# 411618_029_3_5.net
KiCad netlist of a schematic drawn in Altium Designer
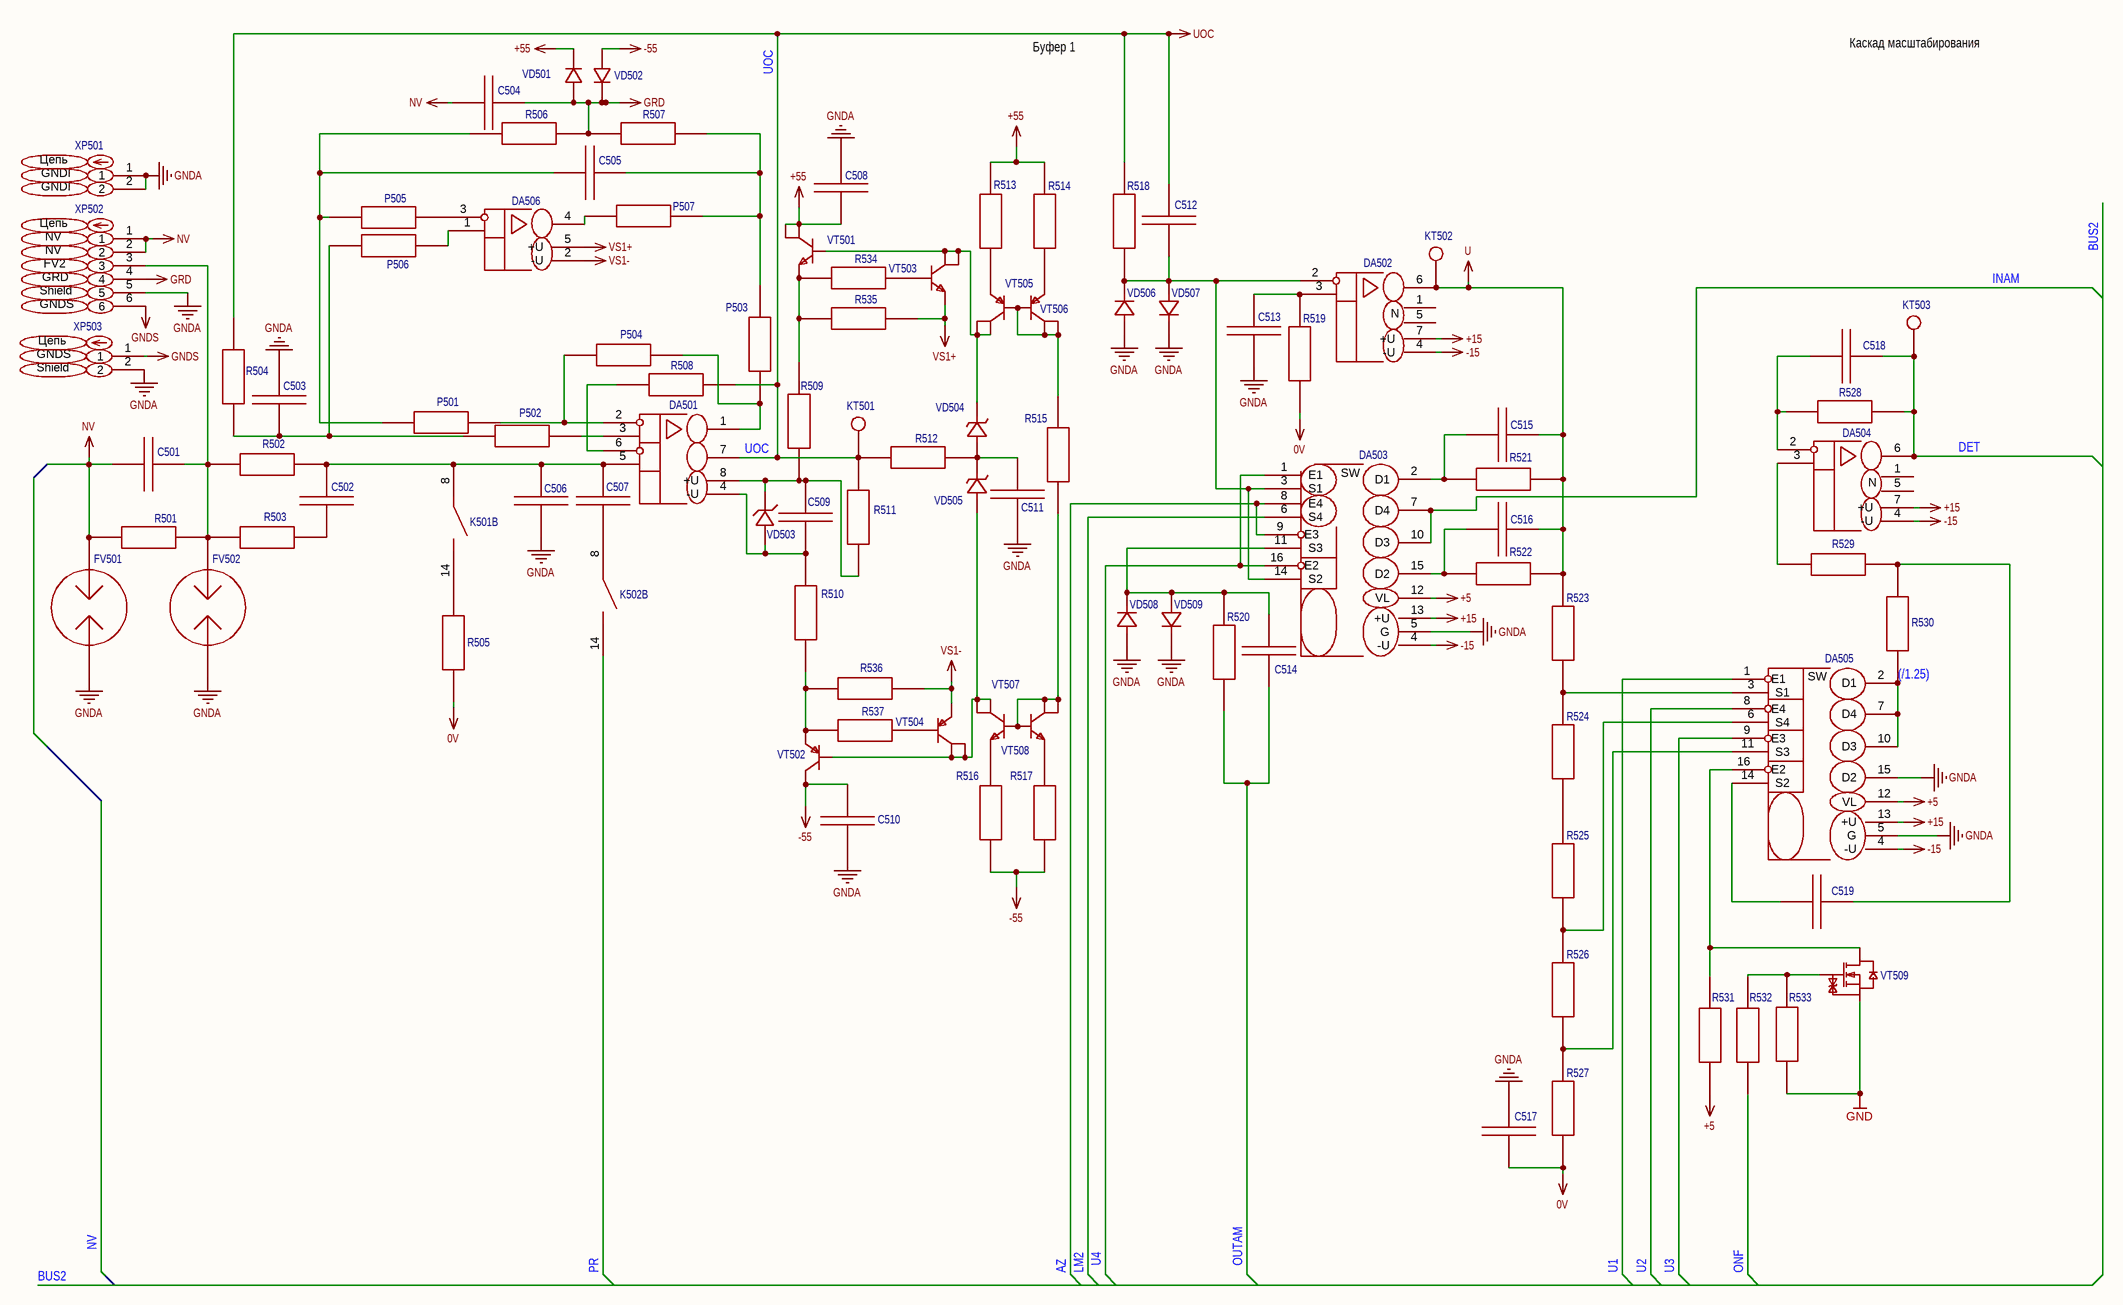
[diagram p0: УШЯИ.411618.029Э Э3 Лист 5.schdoc]

(export (version "E")
  (design (tool "Eeschema 10.0.6"))
  (components
    (comp (ref "C501")
      (value "Конденсатор К10-17Б М47 47пФ  NP0 5% [DIP]")
      (footprint "Конденсатор К10-17Б М47 X.X.xФ  NP0 5% [DIP 8мм]")
      (fields (field (name "MANUFACTURER PART") "К10-17Б М47") (field (name "CONTRIBUTOR") "jordanjin"))
      (libsource (lib "altium-import") (part "root_2_Конденсатор К10-17Б М47 47пФ  NP0 5% [DIP]_"))
    )
    (comp (ref "C502")
      (value "Конденсатор К10-17Б М47 47пФ  NP0 5% [DIP]")
      (footprint "Конденсатор К10-17Б М47 X.X.xФ  NP0 5% [DIP 8мм]")
      (fields (field (name "MANUFACTURER PART") "К10-17Б М47") (field (name "CONTRIBUTOR") "jordanjin"))
      (libsource (lib "altium-import") (part "root_3_Конденсатор К10-17Б М47 47пФ  NP0 5% [DIP]_"))
    )
    (comp (ref "C503")
      (value "Конденсатор SMD 10пФ 100В X7R 10% [0805]")
      (footprint "C0805")
      (fields (field (name "MANUFACTURER PART") "C0805") (field (name "CONTRIBUTOR") "jordanjin"))
      (libsource (lib "altium-import") (part "root_1_Конденсатор SMD 10пФ 100В X7R 10% [0805]_"))
    )
    (comp (ref "C504")
      (value "Конденсатор К10-17Б М47 0,022мкФ  NP0 5% [DIP]")
      (footprint "Конденсатор К10-17Б М47 X.X.xФ  NP0 5% [DIP 5мм]")
      (fields (field (name "MANUFACTURER PART") "К10-17Б М47") (field (name "CONTRIBUTOR") "jordanjin"))
      (libsource (lib "altium-import") (part "root_0_Конденсатор К10-17Б М47 0,022мкФ  NP0 5% [DIP]_"))
    )
    (comp (ref "C505")
      (value "Конденсатор SMD 10пФ 100В X7R 10% [0805]")
      (footprint "C0805")
      (fields (field (name "MANUFACTURER PART") "К10-17Б М47") (field (name "CONTRIBUTOR") "jordanjin"))
      (libsource (lib "altium-import") (part "root_0_Конденсатор К10-17Б М47 10пФ  NP0 5% [DIP]_"))
    )
    (comp (ref "C506")
      (value "Конденсатор К10-17Б М47 33пФ  NP0 5% [DIP]")
      (footprint "Конденсатор К10-17Б М47 X.X.xФ  NP0 5% [DIP 5мм]")
      (fields (field (name "MANUFACTURER PART") "К10-17Б М47") (field (name "CONTRIBUTOR") "jordanjin"))
      (libsource (lib "altium-import") (part "root_3_Конденсатор К10-17Б М47 33пФ  NP0 5% [DIP]_"))
    )
    (comp (ref "C507")
      (value "Конденсатор К10-17Б М47 47пФ  NP0 5% [DIP]")
      (footprint "Конденсатор К10-17Б М47 X.X.xФ  NP0 5% [DIP 5мм]")
      (fields (field (name "MANUFACTURER PART") "К10-17Б М47") (field (name "CONTRIBUTOR") "jordanjin"))
      (libsource (lib "altium-import") (part "root_1_Конденсатор К10-17Б М47 47пФ  NP0 5% [DIP]_"))
    )
    (comp (ref "C508")
      (value "Конденсатор SMD 0,068мкФ 100В X7R 10% [0805]")
      (footprint "C0805")
      (fields (field (name "MANUFACTURER PART") "C0805") (field (name "CONTRIBUTOR") "jordanjin"))
      (libsource (lib "altium-import") (part "root_1_Конденсатор SMD 0,068мкФ 100В X7R 10% [0805]_"))
    )
    (comp (ref "C509")
      (value "Конденсатор SMD 5600пФ 100В X7R 10% [0805]")
      (footprint "C0805")
      (fields (field (name "MANUFACTURER PART") "C0805") (field (name "CONTRIBUTOR") "jordanjin"))
      (libsource (lib "altium-import") (part "root_1_Конденсатор SMD 5600пФ 100В X7R 10% [0805]_"))
    )
    (comp (ref "C510")
      (value "Конденсатор SMD 0,068мкФ 100В X7R 10% [0805]")
      (footprint "C0805")
      (fields (field (name "MANUFACTURER PART") "C0805") (field (name "CONTRIBUTOR") "jordanjin"))
      (libsource (lib "altium-import") (part "root_3_Конденсатор SMD 0,068мкФ 100В X7R 10% [0805]_"))
    )
    (comp (ref "C511")
      (value "Конденсатор SMD 100пФ 100В X7R 10% [0805]")
      (footprint "C0805")
      (fields (field (name "MANUFACTURER PART") "C0805") (field (name "CONTRIBUTOR") "jordanjin"))
      (libsource (lib "altium-import") (part "root_1_Конденсатор SMD 100пФ 100В X7R 10% [0805]_"))
    )
    (comp (ref "C512")
      (value "Конденсатор SMD 10пФ 100В X7R 10% [0805]")
      (footprint "C0805")
      (fields (field (name "MANUFACTURER PART") "C0805") (field (name "CONTRIBUTOR") "jordanjin"))
      (libsource (lib "altium-import") (part "root_1_Конденсатор SMD 10пФ 100В X7R 10% [0805]_"))
    )
    (comp (ref "C513")
      (value "Конденсатор SMD 51пФ 100В X7R 10% [0805]")
      (footprint "C0805")
      (fields (field (name "MANUFACTURER PART") "C0805") (field (name "CONTRIBUTOR") "jordanjin"))
      (libsource (lib "altium-import") (part "root_3_Конденсатор SMD 51пФ 100В X7R 10% [0805]_"))
    )
    (comp (ref "C514")
      (value "Конденсатор SMD 1500пФ 100В X7R 10% [0805]")
      (footprint "C0805")
      (fields (field (name "MANUFACTURER PART") "C0805") (field (name "CONTRIBUTOR") "jordanjin"))
      (libsource (lib "altium-import") (part "root_1_Конденсатор SMD 1500пФ 100В X7R 10% [0805]_"))
    )
    (comp (ref "C515")
      (value "Конденсатор SMD 100пФ 100В X7R 10% [0805]")
      (footprint "C0805")
      (fields (field (name "MANUFACTURER PART") "C0805") (field (name "CONTRIBUTOR") "jordanjin"))
      (libsource (lib "altium-import") (part "root_2_Конденсатор SMD 100пФ 100В X7R 10% [0805]_"))
    )
    (comp (ref "C516")
      (value "Конденсатор SMD 10пФ 100В X7R 10% [0805]")
      (footprint "C0805")
      (fields (field (name "MANUFACTURER PART") "C0805") (field (name "CONTRIBUTOR") "jordanjin"))
      (libsource (lib "altium-import") (part "root_2_Конденсатор SMD 10пФ 100В X7R 10% [0805]_"))
    )
    (comp (ref "C517")
      (value "Конденсатор SMD 240пФ 100В X7R 10% [0805]")
      (footprint "C0805")
      (fields (field (name "MANUFACTURER PART") "C0805") (field (name "CONTRIBUTOR") "jordanjin"))
      (libsource (lib "altium-import") (part "root_3_Конденсатор SMD 240пФ 100В X7R 10% [0805]_"))
    )
    (comp (ref "C518")
      (value "Конденсатор SMD 33пФ 100В X7R 10% [0805]")
      (footprint "C0805")
      (fields (field (name "MANUFACTURER PART") "C0805") (field (name "CONTRIBUTOR") "jordanjin"))
      (libsource (lib "altium-import") (part "root_0_Конденсатор SMD 33пФ 100В X7R 10% [0805]_"))
    )
    (comp (ref "C519")
      (value "Конденсатор SMD 1500пФ 100В X7R 10% [0805]")
      (footprint "C0805")
      (fields (field (name "MANUFACTURER PART") "C0805") (field (name "CONTRIBUTOR") "jordanjin"))
      (libsource (lib "altium-import") (part "root_0_Конденсатор SMD 1500пФ 100В X7R 10% [0805]_"))
    )
    (comp (ref "DA501")
      (value "Операционный усилитель TLV9152IDR [SOIC-8]")
      (footprint "SOIC-8_L4.9-W3.9-P1.27-LS6.0-BL")
      (fields
        (field (name "SUBPART_NO") "1")
        (field (name "MANUFACTURER") "TI")
        (field (name "MANUFACTURER PART") "TLV9152IDR")
        (field (name "CONTRIBUTOR") "jordanjin")
      )
      (libsource (lib "altium-import") (part "root_0_Операционный усилитель TLV9152IDR [SOIC-8]_"))
    )
    (comp (ref "DA502")
      (value "Операционный усилитель ADA4627-1BRZ [SOIC-8]")
      (footprint "SOIC-8_L5.0-W4.0-P1.27-LS6.1-BL")
      (fields
        (field (name "MANUFACTURER") "Analog Devices")
        (field (name "MANUFACTURER PART") "ADA4627-1BRZ")
        (field (name "CONTRIBUTOR") "jordanjin")
      )
      (libsource (lib "altium-import") (part "root_0_Операционный усилитель ADA4627-1BRZ [SOIC-8]_"))
    )
    (comp (ref "DA503")
      (value "Коммутатор аналоговых сигналов ADG433BRZ [SOIC-16]")
      (footprint "SOIC-16_L9.9-W3.9-P1.27-LS6.0-BL")
      (fields
        (field (name "MANUFACTURER") "Analog Devices")
        (field (name "MANUFACTURER PART") "ADG433BRZ-REEL")
        (field (name "CONTRIBUTOR") "jordanjin")
      )
      (libsource (lib "altium-import") (part "root_0_Коммутатор аналоговых сигналов ADG433BRZ [SOIC-16]_"))
    )
    (comp (ref "DA504")
      (value "Операционный усилитель ADA4627-1BRZ [SOIC-8]")
      (footprint "SOIC-8_L5.0-W4.0-P1.27-LS6.1-BL")
      (fields
        (field (name "MANUFACTURER") "Analog Devices")
        (field (name "MANUFACTURER PART") "ADA4627-1BRZ")
        (field (name "CONTRIBUTOR") "jordanjin")
      )
      (libsource (lib "altium-import") (part "root_0_Операционный усилитель ADA4627-1BRZ [SOIC-8]_"))
    )
    (comp (ref "DA505")
      (value "Коммутатор аналоговых сигналов ADG431BRZ [SOIC-16]")
      (footprint "SOIC-16_L9.9-W3.9-P1.27-LS6.0-BL")
      (fields
        (field (name "MANUFACTURER") "Analog Devices")
        (field (name "MANUFACTURER PART") "ADG431BRZ")
        (field (name "CONTRIBUTOR") "jordanjin")
      )
      (libsource (lib "altium-import") (part "root_0_Коммутатор аналоговых сигналов ADG431BRZ [SOIC-16]_"))
    )
    (comp (ref "DA506")
      (value "Операционный усилитель  TLV9151IDCKR [SC-70-5]")
      (footprint "SC-70-5_L2.1-W1.3-P0.65-LS2.2-BR")
      (fields
        (field (name "MANUFACTURER") "TI")
        (field (name "MANUFACTURER PART") "TLV9151IDCKR")
        (field (name "CONTRIBUTOR") "jordanjin")
      )
      (libsource (lib "altium-import") (part "root_0_Операционный усилитель  TLV9151IDCKR [SC-70-5]_"))
    )
    (comp (ref "FV501")
      (value "Разрядник газонаполненный B88069-X8870-B502 (A81-C90X)")
      (fields
        (field (name "MANUFACTURER") "TDK/EPCOS")
        (field (name "MANUFACTURER PART") "B88069-X8870-B502 (A81-C90X)")
        (field (name "CONTRIBUTOR") "jordanjin")
      )
      (libsource (lib "altium-import") (part "root_0_Разрядник газонаполненный B88069-X8870-B502 (A81-C90X)_"))
    )
    (comp (ref "FV502")
      (value "Разрядник газонаполненный B88069-X8870-B502 (A81-C90X)")
      (fields
        (field (name "MANUFACTURER") "TDK/EPCOS")
        (field (name "MANUFACTURER PART") "B88069-X8870-B502 (A81-C90X)")
        (field (name "CONTRIBUTOR") "jordanjin")
      )
      (libsource (lib "altium-import") (part "root_0_Разрядник газонаполненный B88069-X8870-B502 (A81-C90X)_"))
    )
    (comp (ref "K501")
      (value "Реле герконовое DIP05-1A72-13L  [PCB]")
      (footprint "RELAY-TH_STANDEXMEDER_DIP05-1A72-13L")
      (fields
        (field (name "MANUFACTURER") "STANDEXMEDER")
        (field (name "MANUFACTURER PART") "DIP05-1A72-13L")
        (field (name "SUBPART_NO") "2")
        (field (name "CONTRIBUTOR") "jordanjin")
      )
      (libsource (lib "altium-import") (part "root_0_Реле герконовое DIP05-1A72-13L  [PCB]_"))
    )
    (comp (ref "K502")
      (value "Реле герконовое DIP05-1A72-13L  [PCB]")
      (footprint "RELAY-TH_STANDEXMEDER_DIP05-1A72-13L")
      (fields
        (field (name "MANUFACTURER") "STANDEXMEDER")
        (field (name "MANUFACTURER PART") "DIP05-1A72-13L")
        (field (name "SUBPART_NO") "2")
        (field (name "CONTRIBUTOR") "jordanjin")
      )
      (libsource (lib "altium-import") (part "root_0_Реле герконовое DIP05-1A72-13L  [PCB]_"))
    )
    (comp (ref "KT501")
      (value "Control point")
      (fields (field (name "CONTRIBUTOR") "jordanjin"))
      (libsource (lib "altium-import") (part "root_2_Control point_"))
    )
    (comp (ref "KT502")
      (value "Control point")
      (fields (field (name "CONTRIBUTOR") "jordanjin"))
      (libsource (lib "altium-import") (part "root_2_Control point_"))
    )
    (comp (ref "KT503")
      (value "Control point")
      (fields (field (name "CONTRIBUTOR") "jordanjin"))
      (libsource (lib "altium-import") (part "root_2_Control point_"))
    )
    (comp (ref "P501")
      (value "Перемычка")
      (footprint "R0805")
      (fields (field (name "MANUFACTURER PART") "R0805") (field (name "CONTRIBUTOR") "jordanjin"))
      (libsource (lib "altium-import") (part "root_2_Перемычка_"))
    )
    (comp (ref "P502")
      (value "Перемычка")
      (footprint "R0805")
      (fields (field (name "MANUFACTURER PART") "R0805") (field (name "CONTRIBUTOR") "jordanjin"))
      (libsource (lib "altium-import") (part "root_2_Перемычка_"))
    )
    (comp (ref "P503")
      (value "Перемычка")
      (footprint "R0805")
      (fields (field (name "MANUFACTURER PART") "R0805") (field (name "CONTRIBUTOR") "jordanjin"))
      (libsource (lib "altium-import") (part "root_1_Перемычка_"))
    )
    (comp (ref "P504")
      (value "Перемычка")
      (footprint "R0805")
      (fields (field (name "MANUFACTURER PART") "R0805") (field (name "CONTRIBUTOR") "jordanjin"))
      (libsource (lib "altium-import") (part "root_2_Перемычка_"))
    )
    (comp (ref "P505")
      (value "Перемычка")
      (footprint "R0805")
      (fields (field (name "MANUFACTURER PART") "R0805") (field (name "CONTRIBUTOR") "jordanjin"))
      (libsource (lib "altium-import") (part "root_2_Перемычка_"))
    )
    (comp (ref "P506")
      (value "Перемычка")
      (footprint "R0805")
      (fields (field (name "MANUFACTURER PART") "R0805") (field (name "CONTRIBUTOR") "jordanjin"))
      (libsource (lib "altium-import") (part "root_2_Перемычка_"))
    )
    (comp (ref "P507")
      (value "Перемычка")
      (footprint "R0805")
      (fields (field (name "MANUFACTURER PART") "R0805") (field (name "CONTRIBUTOR") "jordanjin"))
      (libsource (lib "altium-import") (part "root_2_Перемычка_"))
    )
    (comp (ref "R501")
      (value "Резистор C2-29В-0,25 1,2кОм ±0,5% [DIP]")
      (fields (field (name "MANUFACTURER PART") "C2-29В-0,25") (field (name "CONTRIBUTOR") "jordanjin"))
      (libsource (lib "altium-import") (part "root_0_Резистор C2-29В-0,25 1,2кОм ±0,5% [DIP]_"))
    )
    (comp (ref "R502")
      (value "Резистор C2-29В-0,25 301кОм ±0,5% [DIP]")
      (fields (field (name "MANUFACTURER PART") "C2-29В-0,25") (field (name "CONTRIBUTOR") "jordanjin"))
      (libsource (lib "altium-import") (part "root_0_Резистор C2-29В-0,25 301кОм ±0,5% [DIP]_"))
    )
    (comp (ref "R503")
      (value "Резистор C2-29В-0,25 5.1кОм ±0,5% [DIP]")
      (fields (field (name "MANUFACTURER PART") "C2-29В-0,25") (field (name "CONTRIBUTOR") "jordanjin"))
      (libsource (lib "altium-import") (part "root_0_Резистор C2-29В-0,25 5.1кОм ±0,5% [DIP]_"))
    )
    (comp (ref "R504")
      (value "Резистор 91кОм 0,125Вт 1% [0805]")
      (footprint "R0805")
      (fields (field (name "MANUFACTURER PART") "R0805") (field (name "CONTRIBUTOR") "jordanjin"))
      (libsource (lib "altium-import") (part "root_1_Резистор 91кОм 0,125Вт 1% [0805]_"))
    )
    (comp (ref "R505")
      (value "Резистор 2.4кОм 0,25Вт 1% [1206]")
      (footprint "R1206")
      (fields (field (name "MANUFACTURER PART") "C2-29В-0,25") (field (name "CONTRIBUTOR") "jordanjin"))
      (libsource (lib "altium-import") (part "root_1_Резистор C2-29В-0,25 2.4кОм ±0,5% [DIP]_"))
    )
    (comp (ref "R506")
      (value "Резистор C2-29В-0,25 51Ом ±0,5% [DIP]")
      (fields (field (name "MANUFACTURER PART") "C2-29В-0,25") (field (name "CONTRIBUTOR") "jordanjin"))
      (libsource (lib "altium-import") (part "root_0_Резистор C2-29В-0,25 51Ом ±0,5% [DIP]_"))
    )
    (comp (ref "R507")
      (value "Резистор C2-29В-0,25 22Ом ±0,5% [DIP]")
      (fields (field (name "MANUFACTURER PART") "C2-29В-0,25") (field (name "CONTRIBUTOR") "jordanjin"))
      (libsource (lib "altium-import") (part "root_0_Резистор C2-29В-0,25 22Ом ±0,5% [DIP]_"))
    )
    (comp (ref "R508")
      (value "Резистор 33Ом 0,125Вт 1% [0805]")
      (footprint "R0805")
      (fields (field (name "MANUFACTURER PART") "R0805") (field (name "CONTRIBUTOR") "jordanjin"))
      (libsource (lib "altium-import") (part "root_0_Резистор 33Ом 0,125Вт 1% [0805]_"))
    )
    (comp (ref "R509")
      (value "Резистор 150Ом 0,125Вт 1% [0805]")
      (footprint "R0805")
      (fields (field (name "MANUFACTURER PART") "R0805") (field (name "CONTRIBUTOR") "jordanjin"))
      (libsource (lib "altium-import") (part "root_1_Резистор 150Ом 0,125Вт 1% [0805]_"))
    )
    (comp (ref "R510")
      (value "Резистор 150Ом 0,125Вт 1% [0805]")
      (footprint "R0805")
      (fields (field (name "MANUFACTURER PART") "R0805") (field (name "CONTRIBUTOR") "jordanjin"))
      (libsource (lib "altium-import") (part "root_1_Резистор 150Ом 0,125Вт 1% [0805]_"))
    )
    (comp (ref "R511")
      (value "Резистор 5,1кОм 0,125Вт 1% [0805]")
      (footprint "R0805")
      (fields (field (name "MANUFACTURER PART") "R0805") (field (name "CONTRIBUTOR") "jordanjin"))
      (libsource (lib "altium-import") (part "root_3_Резистор 5,1кОм 0,125Вт 1% [0805]_"))
    )
    (comp (ref "R512")
      (value "Резистор 4,7кОм 0,125Вт 1% [0805]")
      (footprint "R0805")
      (fields (field (name "MANUFACTURER PART") "R0805") (field (name "CONTRIBUTOR") "jordanjin"))
      (libsource (lib "altium-import") (part "root_0_Резистор 4,7кОм 0,125Вт 1% [0805]_"))
    )
    (comp (ref "R513")
      (value "Резистор 820Ом 0,125Вт 1% [0805]")
      (footprint "R0805")
      (fields (field (name "MANUFACTURER PART") "R0805") (field (name "CONTRIBUTOR") "jordanjin"))
      (libsource (lib "altium-import") (part "root_1_Резистор 820Ом 0,125Вт 1% [0805]_"))
    )
    (comp (ref "R514")
      (value "Резистор 2кОм 0,125Вт 1% [0805]")
      (footprint "R0805")
      (fields (field (name "MANUFACTURER PART") "R0805") (field (name "CONTRIBUTOR") "jordanjin"))
      (libsource (lib "altium-import") (part "root_1_Резистор 2кОм 0,125Вт 1% [0805]_"))
    )
    (comp (ref "R515")
      (value "Резистор 200кОм 0,125Вт 1% [0805]")
      (footprint "R0805")
      (fields (field (name "MANUFACTURER PART") "R0805") (field (name "CONTRIBUTOR") "jordanjin"))
      (libsource (lib "altium-import") (part "root_1_Резистор 200кОм 0,125Вт 1% [0805]_"))
    )
    (comp (ref "R516")
      (value "Резистор 820Ом 0,125Вт 1% [0805]")
      (footprint "R0805")
      (fields (field (name "MANUFACTURER PART") "R0805") (field (name "CONTRIBUTOR") "jordanjin"))
      (libsource (lib "altium-import") (part "root_1_Резистор 820Ом 0,125Вт 1% [0805]_"))
    )
    (comp (ref "R517")
      (value "Резистор 2кОм 0,125Вт 1% [0805]")
      (footprint "R0805")
      (fields (field (name "MANUFACTURER PART") "R0805") (field (name "CONTRIBUTOR") "jordanjin"))
      (libsource (lib "altium-import") (part "root_1_Резистор 2кОм 0,125Вт 1% [0805]_"))
    )
    (comp (ref "R518")
      (value "Резистор 40,2кОм 0.25Вт 1% [1206]")
      (footprint "R0805")
      (fields (field (name "MANUFACTURER PART") "R0805") (field (name "CONTRIBUTOR") "jordanjin"))
      (libsource (lib "altium-import") (part "root_3_Резистор 40,2кОм 0.25Вт 1% [1206]_"))
    )
    (comp (ref "R519")
      (value "Резистор 15кОм 0,125Вт 1% [0805]")
      (footprint "R0805")
      (fields (field (name "MANUFACTURER PART") "R0805") (field (name "CONTRIBUTOR") "jordanjin"))
      (libsource (lib "altium-import") (part "root_1_Резистор 15кОм 0,125Вт 1% [0805]_"))
    )
    (comp (ref "R520")
      (value "Резистор 200кОм 0,125Вт 1% [0805]")
      (footprint "R0805")
      (fields (field (name "MANUFACTURER PART") "R0805") (field (name "CONTRIBUTOR") "jordanjin"))
      (libsource (lib "altium-import") (part "root_3_Резистор 200кОм 0,125Вт 1% [0805]_"))
    )
    (comp (ref "R521")
      (value "Резистор 10кОм 0,125Вт 1% [0805]")
      (footprint "R0805")
      (fields (field (name "MANUFACTURER PART") "R0805") (field (name "CONTRIBUTOR") "jordanjin"))
      (libsource (lib "altium-import") (part "root_0_Резистор 10кОм 0,125Вт 1% [0805]_"))
    )
    (comp (ref "R522")
      (value "Резистор 100кОм 0,125Вт 1% [0805]")
      (footprint "R0805")
      (fields (field (name "MANUFACTURER PART") "R0805") (field (name "CONTRIBUTOR") "jordanjin"))
      (libsource (lib "altium-import") (part "root_0_Резистор 100кОм 0,125Вт 1% [0805]_"))
    )
    (comp (ref "R523")
      (value "Резистор 4,02кОм 0.25Вт 1% [1206]")
      (footprint "R1206")
      (fields (field (name "MANUFACTURER PART") "R1206") (field (name "CONTRIBUTOR") "jordanjin"))
      (libsource (lib "altium-import") (part "root_1_Резистор 4,02кОм 0.25Вт 1% [1206]_"))
    )
    (comp (ref "R524")
      (value "Резистор 4,02кОм 0.25Вт 1% [1206]")
      (footprint "R1206")
      (fields (field (name "MANUFACTURER PART") "R1206") (field (name "CONTRIBUTOR") "jordanjin"))
      (libsource (lib "altium-import") (part "root_1_Резистор 4,02кОм 0.25Вт 1% [1206]_"))
    )
    (comp (ref "R525")
      (value "Резистор 4,02кОм 0.25Вт 1% [1206]")
      (footprint "R1206")
      (fields (field (name "MANUFACTURER PART") "R1206") (field (name "CONTRIBUTOR") "jordanjin"))
      (libsource (lib "altium-import") (part "root_1_Резистор 4,02кОм 0.25Вт 1% [1206]_"))
    )
    (comp (ref "R526")
      (value "Резистор 4,02кОм 0.25Вт 1% [1206]")
      (footprint "R1206")
      (fields (field (name "MANUFACTURER PART") "R1206") (field (name "CONTRIBUTOR") "jordanjin"))
      (libsource (lib "altium-import") (part "root_1_Резистор 4,02кОм 0.25Вт 1% [1206]_"))
    )
    (comp (ref "R527")
      (value "Резистор 4,02кОм 0.25Вт 1% [1206]")
      (footprint "R1206")
      (fields (field (name "MANUFACTURER PART") "R1206") (field (name "CONTRIBUTOR") "jordanjin"))
      (libsource (lib "altium-import") (part "root_1_Резистор 4,02кОм 0.25Вт 1% [1206]_"))
    )
    (comp (ref "R528")
      (value "Резистор 3,6кОм 0,125Вт 1% [0805]")
      (footprint "R0805")
      (fields (field (name "MANUFACTURER PART") "R0805") (field (name "CONTRIBUTOR") "jordanjin"))
      (libsource (lib "altium-import") (part "root_2_Резистор 3,6кОм 0,125Вт 1% [0805]_"))
    )
    (comp (ref "R529")
      (value "Резистор 110кОм 0,125Вт 1% [0805]")
      (footprint "R0805")
      (fields (field (name "MANUFACTURER PART") "R0805") (field (name "CONTRIBUTOR") "jordanjin"))
      (libsource (lib "altium-import") (part "root_2_Резистор 110кОм 0,125Вт 1% [0805]_"))
    )
    (comp (ref "R530")
      (value "Резистор 110кОм 0,125Вт 1% [0805]")
      (footprint "R0805")
      (fields (field (name "MANUFACTURER PART") "R0805") (field (name "CONTRIBUTOR") "jordanjin"))
      (libsource (lib "altium-import") (part "root_1_Резистор 110кОм 0,125Вт 1% [0805]_"))
    )
    (comp (ref "R531")
      (value "Резистор 5,3кОм 0,125Вт 1% [0805]")
      (footprint "R0805")
      (fields (field (name "MANUFACTURER PART") "R0805") (field (name "CONTRIBUTOR") "jordanjin"))
      (libsource (lib "altium-import") (part "root_1_Резистор 5,3кОм 0,125Вт 1% [0805]_"))
    )
    (comp (ref "R532")
      (value "Резистор 100Ом 0,125Вт 1% [0805]")
      (footprint "R0805")
      (fields (field (name "MANUFACTURER PART") "R0805") (field (name "CONTRIBUTOR") "jordanjin"))
      (libsource (lib "altium-import") (part "root_1_Резистор 100Ом 0,125Вт 1% [0805]_"))
    )
    (comp (ref "R533")
      (value "Резистор 100Ом 0,125Вт 1% [0805]")
      (footprint "R0805")
      (fields (field (name "MANUFACTURER PART") "R0805") (field (name "CONTRIBUTOR") "jordanjin"))
      (libsource (lib "altium-import") (part "root_1_Резистор 100Ом 0,125Вт 1% [0805]_"))
    )
    (comp (ref "R534")
      (value "Резистор 400Ом 0,125Вт 1% [0805]")
      (footprint "R0805")
      (fields (field (name "MANUFACTURER PART") "R0805") (field (name "CONTRIBUTOR") "jordanjin"))
      (libsource (lib "altium-import") (part "root_2_Резистор 400Ом 0,125Вт 1% [0805]_"))
    )
    (comp (ref "R535")
      (value "Резистор 150Ом 0,125Вт 1% [0805]")
      (footprint "R0805")
      (fields (field (name "MANUFACTURER PART") "R0805") (field (name "CONTRIBUTOR") "jordanjin"))
      (libsource (lib "altium-import") (part "root_2_Резистор 150Ом 0,125Вт 1% [0805]_"))
    )
    (comp (ref "R536")
      (value "Резистор 150Ом 0,125Вт 1% [0805]")
      (footprint "R0805")
      (fields (field (name "MANUFACTURER PART") "R0805") (field (name "CONTRIBUTOR") "jordanjin"))
      (libsource (lib "altium-import") (part "root_2_Резистор 150Ом 0,125Вт 1% [0805]_"))
    )
    (comp (ref "R537")
      (value "Резистор 400Ом 0,125Вт 1% [0805]")
      (footprint "R0805")
      (fields (field (name "MANUFACTURER PART") "R0805") (field (name "CONTRIBUTOR") "jordanjin"))
      (libsource (lib "altium-import") (part "root_2_Резистор 400Ом 0,125Вт 1% [0805]_"))
    )
    (comp (ref "VD501")
      (value "Диод импульсный 1N4448 [DO-35]")
      (footprint "DO-35_BD2.0-L4.2-P8.20-D0.5-RD")
      (fields
        (field (name "MANUFACTURER") "onsemi")
        (field (name "MANUFACTURER PART") "1N4448TR")
        (field (name "CONTRIBUTOR") "jordanjin")
      )
      (libsource (lib "altium-import") (part "root_3_Диод импульсный 1N4448 [DO-35]_"))
    )
    (comp (ref "VD502")
      (value "Диод импульсный 1N4448 [DO-35]")
      (footprint "DO-35_BD2.0-L4.2-P8.20-D0.5-RD")
      (fields
        (field (name "MANUFACTURER") "onsemi")
        (field (name "MANUFACTURER PART") "1N4448TR")
        (field (name "CONTRIBUTOR") "jordanjin")
      )
      (libsource (lib "altium-import") (part "root_1_Диод импульсный 1N4448 [DO-35]_"))
    )
    (comp (ref "VD503")
      (value "Стабилитрон MMSZ5230B 4.7В 0.5Вт [SOD123]")
      (footprint "SOD-123_L2.8-W1.8-LS3.7-RD")
      (fields (field (name "MANUFACTURER PART") "MMSZ5230B") (field (name "MANUFACTURER") "CJ(江苏长电/长晶)"))
      (libsource (lib "altium-import") (part "root_3_Стабилитрон MMSZ5230B 4.7В 0.5Вт [SOD123]_"))
    )
    (comp (ref "VD504")
      (value "Стабилитрон MMSZ5232B 5.6В 0.5Вт [SOD123]")
      (footprint "SOD-123_L2.7-W1.6-LS3.7-RD")
      (fields
        (field (name "MANUFACTURER") "MCC(美微科)")
        (field (name "MANUFACTURER PART") "MMSZ5232B-TP")
        (field (name "CONTRIBUTOR") "LCSC")
      )
      (libsource (lib "altium-import") (part "root_3_Стабилитрон MMSZ5232B 5.6В 0.5Вт [SOD123]_"))
    )
    (comp (ref "VD505")
      (value "Стабилитрон MMSZ5232B 5.6В 0.5Вт [SOD123]")
      (footprint "SOD-123_L2.7-W1.6-LS3.7-RD")
      (fields
        (field (name "MANUFACTURER") "MCC(美微科)")
        (field (name "MANUFACTURER PART") "MMSZ5232B-TP")
        (field (name "CONTRIBUTOR") "LCSC")
      )
      (libsource (lib "altium-import") (part "root_3_Стабилитрон MMSZ5232B 5.6В 0.5Вт [SOD123]_"))
    )
    (comp (ref "VD506")
      (value "Диод импульсный 1N4448 [SOD-123]")
      (footprint "SOD-123_L2.7-W1.6-LS3.7-RD-1")
      (fields
        (field (name "MANUFACTURER") "YANGJIE")
        (field (name "MANUFACTURER PART") "1N4448WQ")
        (field (name "CONTRIBUTOR") "jordanjin")
      )
      (libsource (lib "altium-import") (part "root_3_Диод импульсный 1N4448 [SOD-123]_"))
    )
    (comp (ref "VD507")
      (value "Диод импульсный 1N4448 [SOD-123]")
      (footprint "SOD-123_L2.7-W1.6-LS3.7-RD-1")
      (fields
        (field (name "MANUFACTURER") "YANGJIE")
        (field (name "MANUFACTURER PART") "1N4448WQ")
        (field (name "CONTRIBUTOR") "jordanjin")
      )
      (libsource (lib "altium-import") (part "root_1_Диод импульсный 1N4448 [SOD-123]_"))
    )
    (comp (ref "VD508")
      (value "Диод импульсный 1N4448 [SOD-123]")
      (footprint "SOD-123_L2.7-W1.6-LS3.7-RD-1")
      (fields
        (field (name "MANUFACTURER") "YANGJIE")
        (field (name "MANUFACTURER PART") "1N4448WQ")
        (field (name "CONTRIBUTOR") "jordanjin")
      )
      (libsource (lib "altium-import") (part "root_3_Диод импульсный 1N4448 [SOD-123]_"))
    )
    (comp (ref "VD509")
      (value "Диод импульсный 1N4448 [SOD-123]")
      (footprint "SOD-123_L2.7-W1.6-LS3.7-RD-1")
      (fields
        (field (name "MANUFACTURER") "YANGJIE")
        (field (name "MANUFACTURER PART") "1N4448WQ")
        (field (name "CONTRIBUTOR") "jordanjin")
      )
      (libsource (lib "altium-import") (part "root_1_Диод импульсный 1N4448 [SOD-123]_"))
    )
    (comp (ref "VT501")
      (value "Транзистор DZT658 NPN [SOT223]")
      (footprint "SOT-223-3_L6.5-W3.4-P2.30-LS7.0-BR")
      (fields
        (field (name "MANUFACTURER") "DIODES(美台)")
        (field (name "MANUFACTURER PART") "DZT658-13")
        (field (name "CONTRIBUTOR") "LCSC")
      )
      (libsource (lib "altium-import") (part "root_0_Транзистор DZT658 NPN [SOT223]_"))
    )
    (comp (ref "VT502")
      (value "Транзистор FZT758 PNP [SOT223]")
      (footprint "SOT-223_L6.5-W3.5-P2.30-LS7.0-BR")
      (fields
        (field (name "MANUFACTURER") "DIODES(美台)")
        (field (name "MANUFACTURER PART") "FZT758TA")
        (field (name "CONTRIBUTOR") "LCSC")
      )
      (libsource (lib "altium-import") (part "root_0_Транзистор FZT758 PNP [SOT223]_"))
    )
    (comp (ref "VT503")
      (value "Транзистор DZTA42 NPN [SOT223]")
      (footprint "SOT-223-4_L6.5-W3.5-P2.30-LS7.0-BR")
      (fields
        (field (name "MANUFACTURER") "DIODES(美台)")
        (field (name "MANUFACTURER PART") "DZTA42-13")
        (field (name "CONTRIBUTOR") "LCSC")
      )
      (libsource (lib "altium-import") (part "root_0_Транзистор DZTA42 NPN [SOT223]_"))
    )
    (comp (ref "VT504")
      (value "Транзистор DZTA92 PNP [SOT223]")
      (footprint "SOT-223-3_L6.5-W3.4-P2.30-LS7.0-BR")
      (fields
        (field (name "MANUFACTURER") "DIODES(美台)")
        (field (name "MANUFACTURER PART") "DZTA92-13")
        (field (name "CONTRIBUTOR") "lcsc")
      )
      (libsource (lib "altium-import") (part "root_0_Транзистор DZTA92 PNP [SOT223]_"))
    )
    (comp (ref "VT505")
      (value "Транзистор DZTA92 PNP [SOT223]")
      (footprint "SOT-223-3_L6.5-W3.4-P2.30-LS7.0-BR")
      (fields
        (field (name "MANUFACTURER") "DIODES(美台)")
        (field (name "MANUFACTURER PART") "DZTA92-13")
        (field (name "CONTRIBUTOR") "lcsc")
      )
      (libsource (lib "") (part "root_0_Транзистор DZTA92 PNP [SOT223]__1"))
    )
    (comp (ref "VT506")
      (value "Транзистор DZTA92 PNP [SOT223]")
      (footprint "SOT-223-3_L6.5-W3.4-P2.30-LS7.0-BR")
      (fields
        (field (name "MANUFACTURER") "DIODES(美台)")
        (field (name "MANUFACTURER PART") "DZTA92-13")
        (field (name "CONTRIBUTOR") "lcsc")
      )
      (libsource (lib "altium-import") (part "root_0_Транзистор DZTA92 PNP [SOT223]_"))
    )
    (comp (ref "VT507")
      (value "Транзистор DZTA42 NPN [SOT223]")
      (footprint "SOT-223-4_L6.5-W3.5-P2.30-LS7.0-BR")
      (fields
        (field (name "MANUFACTURER") "DIODES(美台)")
        (field (name "MANUFACTURER PART") "DZTA42-13")
        (field (name "CONTRIBUTOR") "LCSC")
      )
      (libsource (lib "") (part "root_0_Транзистор DZTA42 NPN [SOT223]__1"))
    )
    (comp (ref "VT508")
      (value "Транзистор DZTA42 NPN [SOT223]")
      (footprint "SOT-223-4_L6.5-W3.5-P2.30-LS7.0-BR")
      (fields
        (field (name "MANUFACTURER") "DIODES(美台)")
        (field (name "MANUFACTURER PART") "DZTA42-13")
        (field (name "CONTRIBUTOR") "LCSC")
      )
      (libsource (lib "altium-import") (part "root_0_Транзистор DZTA42 NPN [SOT223]_"))
    )
    (comp (ref "VT509")
      (value "Транзистор полевой MOSFET N-канальный BSS138BK [SOT-23-3]")
      (footprint "SOT-23-3_L2.9-W1.3-P1.90-LS2.4-BR")
      (fields
        (field (name "MANUFACTURER") "ElecSuper(静芯)")
        (field (name "MANUFACTURER PART") "BSS138BK")
        (field (name "CONTRIBUTOR") "lcsc")
      )
      (libsource (lib "altium-import") (part "root_0_Транзистор полевой MOSFET N-канальный BSS138BK [SOT-23-3]_"))
    )
    (comp (ref "XP501")
      (value "Вилка на плату 280370-2 шаг 2.54мм")
      (footprint "CONN-TH_280370-2")
      (fields
        (field (name "MANUFACTURER") "TE Connectivity")
        (field (name "MANUFACTURER PART") "280370-2")
        (field (name "CONTRIBUTOR") "jordanjin")
      )
      (libsource (lib "altium-import") (part "root_0_Вилка на плату 280370-2 шаг 2.54мм_"))
    )
    (comp (ref "XP502")
      (value "Вилка на плату 280372-1 шаг 2.54мм")
      (footprint "CONN-TH_280372-1")
      (fields
        (field (name "MANUFACTURER") "TE Connectivity")
        (field (name "MANUFACTURER PART") "280372-1")
        (field (name "CONTRIBUTOR") "jordanjin")
      )
      (libsource (lib "altium-import") (part "root_0_Вилка на плату 280372-1 шаг 2.54мм_"))
    )
    (comp (ref "XP503")
      (value "Вилка на плату 280370-2 шаг 2.54мм")
      (footprint "CONN-TH_280370-2")
      (fields
        (field (name "MANUFACTURER") "TE Connectivity")
        (field (name "MANUFACTURER PART") "280370-2")
        (field (name "CONTRIBUTOR") "jordanjin")
      )
      (libsource (lib "altium-import") (part "root_0_Вилка на плату 280370-2 шаг 2.54мм_"))
    )
  )
  (nets
    (net (code "2") (name "+5") (class "Default")
      (node (ref "DA503") (pin "12") (pinfunction "VL_12") (pintype "passive"))
      (node (ref "DA505") (pin "12") (pinfunction "VL_12") (pintype "passive"))
      (node (ref "R531") (pin "1") (pinfunction "1_1") (pintype "passive"))
    )
    (net (code "3") (name "+15") (class "Default")
      (node (ref "DA502") (pin "7") (pinfunction "+U_7") (pintype "passive"))
      (node (ref "DA503") (pin "13") (pinfunction "+U_13") (pintype "passive"))
      (node (ref "DA504") (pin "7") (pinfunction "+U_7") (pintype "passive"))
      (node (ref "DA505") (pin "13") (pinfunction "+U_13") (pintype "passive"))
    )
    (net (code "4") (name "+55") (class "Default")
      (node (ref "C508") (pin "1") (pinfunction "1_1") (pintype "passive"))
      (node (ref "R513") (pin "2") (pinfunction "2_2") (pintype "passive"))
      (node (ref "R514") (pin "2") (pinfunction "2_2") (pintype "passive"))
      (node (ref "VD501") (pin "1") (pinfunction "1_1") (pintype "passive"))
      (node (ref "VT501") (pin "2") (pinfunction "C_2") (pintype "passive"))
      (node (ref "VT501") (pin "4") (pinfunction "C_4") (pintype "passive"))
    )
    (net (code "5") (name "-15") (class "Default")
      (node (ref "DA502") (pin "4") (pinfunction "-U_4") (pintype "passive"))
      (node (ref "DA503") (pin "4") (pinfunction "-U_4") (pintype "passive"))
      (node (ref "DA504") (pin "4") (pinfunction "-U_4") (pintype "passive"))
      (node (ref "DA505") (pin "4") (pinfunction "-U_4") (pintype "passive"))
    )
    (net (code "6") (name "-55") (class "Default")
      (node (ref "C510") (pin "1") (pinfunction "1_1") (pintype "passive"))
      (node (ref "R516") (pin "1") (pinfunction "1_1") (pintype "passive"))
      (node (ref "R517") (pin "1") (pinfunction "1_1") (pintype "passive"))
      (node (ref "VD502") (pin "2") (pinfunction "2_2") (pintype "passive"))
      (node (ref "VT502") (pin "2") (pinfunction "C_2") (pintype "passive"))
      (node (ref "VT502") (pin "4") (pinfunction "C_4") (pintype "passive"))
    )
    (net (code "7") (name "/({slash}1.25)") (class "Default")
      (node (ref "DA505") (pin "10") (pinfunction "D3_10") (pintype "passive"))
      (node (ref "DA505") (pin "2") (pinfunction "D1_2") (pintype "passive"))
      (node (ref "DA505") (pin "7") (pinfunction "D4_7") (pintype "passive"))
      (node (ref "R530") (pin "1") (pinfunction "1_1") (pintype "passive"))
    )
    (net (code "8") (name "/AZ") (class "Default")
      (node (ref "DA503") (pin "8") (pinfunction "E4_8") (pintype "passive"))
      (node (ref "DA503") (pin "9") (pinfunction "E3_9") (pintype "passive"))
    )
    (net (code "9") (name "/DET") (class "Default")
      (node (ref "C518") (pin "2") (pinfunction "2_2") (pintype "passive"))
      (node (ref "DA504") (pin "6") (pinfunction "OUT_6") (pintype "passive"))
      (node (ref "KT503") (pin "1") (pinfunction "1_1") (pintype "passive"))
      (node (ref "R528") (pin "1") (pinfunction "1_1") (pintype "passive"))
    )
    (net (code "10") (name "/INAM") (class "Default")
      (node (ref "DA503") (pin "10") (pinfunction "D3_10") (pintype "passive"))
      (node (ref "DA503") (pin "7") (pinfunction "D4_7") (pintype "passive"))
    )
    (net (code "11") (name "/LM2") (class "Default")
      (node (ref "DA503") (pin "6") (pinfunction "S4_6") (pintype "passive"))
    )
    (net (code "12") (name "/ONF") (class "Default")
      (node (ref "R532") (pin "1") (pinfunction "1_1") (pintype "passive"))
    )
    (net (code "13") (name "/OUTAM") (class "Default")
      (node (ref "C514") (pin "1") (pinfunction "1_1") (pintype "passive"))
      (node (ref "R520") (pin "2") (pinfunction "2_2") (pintype "passive"))
    )
    (net (code "14") (name "/PR") (class "Default")
      (node (ref "K502") (pin "14") (pinfunction "14_14") (pintype "passive"))
    )
    (net (code "15") (name "/U1") (class "Default")
      (node (ref "DA505") (pin "1") (pinfunction "E1_1") (pintype "passive"))
    )
    (net (code "16") (name "/U2") (class "Default")
      (node (ref "DA505") (pin "8") (pinfunction "E4_8") (pintype "passive"))
    )
    (net (code "17") (name "/U3") (class "Default")
      (node (ref "DA505") (pin "9") (pinfunction "E3_9") (pintype "passive"))
    )
    (net (code "18") (name "/U4") (class "Default")
      (node (ref "DA503") (pin "1") (pinfunction "E1_1") (pintype "passive"))
      (node (ref "DA503") (pin "16") (pinfunction "E2_16") (pintype "passive"))
    )
    (net (code "20") (name "0V") (class "Default")
      (node (ref "C517") (pin "2") (pinfunction "2_2") (pintype "passive"))
      (node (ref "R505") (pin "1") (pinfunction "1_1") (pintype "passive"))
      (node (ref "R519") (pin "1") (pinfunction "1_1") (pintype "passive"))
      (node (ref "R527") (pin "1") (pinfunction "1_1") (pintype "passive"))
    )
    (net (code "21") (name "GND") (class "Default")
      (node (ref "R533") (pin "1") (pinfunction "1_1") (pintype "passive"))
      (node (ref "VT509") (pin "2") (pinfunction "S_2") (pintype "passive"))
    )
    (net (code "22") (name "GNDA") (class "Default")
      (node (ref "C503") (pin "2") (pinfunction "2_2") (pintype "passive"))
      (node (ref "C506") (pin "2") (pinfunction "2_2") (pintype "passive"))
      (node (ref "C508") (pin "2") (pinfunction "2_2") (pintype "passive"))
      (node (ref "C510") (pin "2") (pinfunction "2_2") (pintype "passive"))
      (node (ref "C511") (pin "1") (pinfunction "1_1") (pintype "passive"))
      (node (ref "C513") (pin "2") (pinfunction "2_2") (pintype "passive"))
      (node (ref "C517") (pin "1") (pinfunction "1_1") (pintype "passive"))
      (node (ref "DA503") (pin "5") (pinfunction "G_5") (pintype "passive"))
      (node (ref "DA505") (pin "15") (pinfunction "D2_15") (pintype "passive"))
      (node (ref "DA505") (pin "5") (pinfunction "G_5") (pintype "passive"))
      (node (ref "FV501") (pin "2") (pinfunction "2_2") (pintype "passive"))
      (node (ref "FV502") (pin "2") (pinfunction "2_2") (pintype "passive"))
      (node (ref "VD506") (pin "2") (pinfunction "A_2") (pintype "passive"))
      (node (ref "VD507") (pin "1") (pinfunction "C_1") (pintype "passive"))
      (node (ref "VD508") (pin "2") (pinfunction "A_2") (pintype "passive"))
      (node (ref "VD509") (pin "1") (pinfunction "C_1") (pintype "passive"))
      (node (ref "XP501") (pin "1") (pinfunction "1_1") (pintype "passive"))
      (node (ref "XP501") (pin "2") (pinfunction "2_2") (pintype "passive"))
      (node (ref "XP502") (pin "5") (pinfunction "5_5") (pintype "passive"))
      (node (ref "XP503") (pin "2") (pinfunction "2_2") (pintype "passive"))
    )
    (net (code "23") (name "GNDS") (class "Default")
      (node (ref "XP502") (pin "6") (pinfunction "6_6") (pintype "passive"))
      (node (ref "XP503") (pin "1") (pinfunction "1_1") (pintype "passive"))
    )
    (net (code "24") (name "GRD") (class "Default")
      (node (ref "C504") (pin "2") (pinfunction "2_2") (pintype "passive"))
      (node (ref "R506") (pin "2") (pinfunction "2_2") (pintype "passive"))
      (node (ref "R507") (pin "1") (pinfunction "1_1") (pintype "passive"))
      (node (ref "VD501") (pin "2") (pinfunction "2_2") (pintype "passive"))
      (node (ref "VD502") (pin "1") (pinfunction "1_1") (pintype "passive"))
      (node (ref "XP502") (pin "4") (pinfunction "4_4") (pintype "passive"))
    )
    (net (code "25") (name "NV") (class "Default")
      (node (ref "C501") (pin "2") (pinfunction "2_2") (pintype "passive"))
      (node (ref "C504") (pin "1") (pinfunction "1_1") (pintype "passive"))
      (node (ref "FV501") (pin "1") (pinfunction "1_1") (pintype "passive"))
      (node (ref "R501") (pin "1") (pinfunction "1_1") (pintype "passive"))
      (node (ref "XP502") (pin "1") (pinfunction "1_1") (pintype "passive"))
      (node (ref "XP502") (pin "2") (pinfunction "2_2") (pintype "passive"))
    )
    (net (code "26") (name "Net-(C501-Pad1)") (class "Default")
      (node (ref "C501") (pin "1") (pinfunction "1_1") (pintype "passive"))
      (node (ref "FV502") (pin "1") (pinfunction "1_1") (pintype "passive"))
      (node (ref "R501") (pin "2") (pinfunction "2_2") (pintype "passive"))
      (node (ref "R502") (pin "1") (pinfunction "1_1") (pintype "passive"))
      (node (ref "R503") (pin "1") (pinfunction "1_1") (pintype "passive"))
      (node (ref "XP502") (pin "3") (pinfunction "3_3") (pintype "passive"))
    )
    (net (code "27") (name "Net-(C502-Pad1)") (class "Default")
      (node (ref "C502") (pin "1") (pinfunction "1_1") (pintype "passive"))
      (node (ref "C506") (pin "1") (pinfunction "1_1") (pintype "passive"))
      (node (ref "C507") (pin "2") (pinfunction "2_2") (pintype "passive"))
      (node (ref "DA501") (pin "5") (pinfunction "+IN_5") (pintype "passive"))
      (node (ref "K501") (pin "8") (pinfunction "8_8") (pintype "passive"))
      (node (ref "R502") (pin "2") (pinfunction "2_2") (pintype "passive"))
    )
    (net (code "28") (name "Net-(C502-Pad2)") (class "Default")
      (node (ref "C502") (pin "2") (pinfunction "2_2") (pintype "passive"))
      (node (ref "R503") (pin "2") (pinfunction "2_2") (pintype "passive"))
    )
    (net (code "29") (name "Net-(C503-Pad1)") (class "Default")
      (node (ref "C503") (pin "1") (pinfunction "1_1") (pintype "passive"))
      (node (ref "P502") (pin "2") (pinfunction "2_2") (pintype "passive"))
      (node (ref "P506") (pin "2") (pinfunction "2_2") (pintype "passive"))
      (node (ref "R504") (pin "1") (pinfunction "1_1") (pintype "passive"))
    )
    (net (code "30") (name "Net-(C505-Pad1)") (class "Default")
      (node (ref "C505") (pin "1") (pinfunction "1_1") (pintype "passive"))
      (node (ref "P501") (pin "2") (pinfunction "2_2") (pintype "passive"))
      (node (ref "P505") (pin "2") (pinfunction "2_2") (pintype "passive"))
      (node (ref "R506") (pin "1") (pinfunction "1_1") (pintype "passive"))
    )
    (net (code "31") (name "Net-(C505-Pad2)") (class "Default")
      (node (ref "C505") (pin "2") (pinfunction "2_2") (pintype "passive"))
      (node (ref "P503") (pin "2") (pinfunction "2_2") (pintype "passive"))
      (node (ref "P507") (pin "1") (pinfunction "1_1") (pintype "passive"))
      (node (ref "R507") (pin "2") (pinfunction "2_2") (pintype "passive"))
    )
    (net (code "32") (name "Net-(C507-Pad1)") (class "Default")
      (node (ref "C507") (pin "1") (pinfunction "1_1") (pintype "passive"))
      (node (ref "K502") (pin "8") (pinfunction "8_8") (pintype "passive"))
    )
    (net (code "33") (name "Net-(C519-Pad2)") (class "Default")
      (node (ref "C519") (pin "2") (pinfunction "2_2") (pintype "passive"))
      (node (ref "R529") (pin "1") (pinfunction "1_1") (pintype "passive"))
      (node (ref "R530") (pin "2") (pinfunction "2_2") (pintype "passive"))
    )
    (net (code "34") (name "Net-(DA501-+IN-Pad3)") (class "Default")
      (node (ref "DA501") (pin "3") (pinfunction "+IN_3") (pintype "passive"))
      (node (ref "P502") (pin "1") (pinfunction "1_1") (pintype "passive"))
    )
    (net (code "35") (name "Net-(DA501-+U)") (class "Default")
      (node (ref "C509") (pin "2") (pinfunction "2_2") (pintype "passive"))
      (node (ref "DA501") (pin "8") (pinfunction "+U_8") (pintype "passive"))
      (node (ref "R509") (pin "1") (pinfunction "1_1") (pintype "passive"))
      (node (ref "R511") (pin "2") (pinfunction "2_2") (pintype "passive"))
      (node (ref "VD503") (pin "1") (pinfunction "K_1") (pintype "passive"))
    )
    (net (code "36") (name "Net-(DA501--IN-Pad2)") (class "Default")
      (node (ref "DA501") (pin "2") (pinfunction "-IN_2") (pintype "passive"))
      (node (ref "P501") (pin "1") (pinfunction "1_1") (pintype "passive"))
      (node (ref "P504") (pin "2") (pinfunction "2_2") (pintype "passive"))
    )
    (net (code "37") (name "Net-(DA501--IN-Pad6)") (class "Default")
      (node (ref "DA501") (pin "6") (pinfunction "-IN_6") (pintype "passive"))
      (node (ref "R508") (pin "1") (pinfunction "1_1") (pintype "passive"))
    )
    (net (code "38") (name "Net-(DA501--U)") (class "Default")
      (node (ref "C509") (pin "1") (pinfunction "1_1") (pintype "passive"))
      (node (ref "DA501") (pin "4") (pinfunction "-U_4") (pintype "passive"))
      (node (ref "R510") (pin "2") (pinfunction "2_2") (pintype "passive"))
      (node (ref "VD503") (pin "2") (pinfunction "A_2") (pintype "passive"))
    )
    (net (code "39") (name "Net-(DA501-OUT-Pad1)") (class "Default")
      (node (ref "DA501") (pin "1") (pinfunction "OUT_1") (pintype "passive"))
      (node (ref "P503") (pin "1") (pinfunction "1_1") (pintype "passive"))
      (node (ref "P504") (pin "1") (pinfunction "1_1") (pintype "passive"))
    )
    (net (code "40") (name "Net-(DA502-+IN)") (class "Default")
      (node (ref "C513") (pin "1") (pinfunction "1_1") (pintype "passive"))
      (node (ref "DA502") (pin "3") (pinfunction "+IN_3") (pintype "passive"))
      (node (ref "R519") (pin "2") (pinfunction "2_2") (pintype "passive"))
    )
    (net (code "41") (name "Net-(DA502--IN)") (class "Default")
      (node (ref "C512") (pin "1") (pinfunction "1_1") (pintype "passive"))
      (node (ref "DA502") (pin "2") (pinfunction "-IN_2") (pintype "passive"))
      (node (ref "DA503") (pin "14") (pinfunction "S2_14") (pintype "passive"))
      (node (ref "DA503") (pin "3") (pinfunction "S1_3") (pintype "passive"))
      (node (ref "R518") (pin "2") (pinfunction "2_2") (pintype "passive"))
      (node (ref "VD506") (pin "1") (pinfunction "C_1") (pintype "passive"))
      (node (ref "VD507") (pin "2") (pinfunction "A_2") (pintype "passive"))
    )
    (net (code "42") (name "Net-(DA503-D1)") (class "Default")
      (node (ref "C515") (pin "2") (pinfunction "2_2") (pintype "passive"))
      (node (ref "DA503") (pin "2") (pinfunction "D1_2") (pintype "passive"))
      (node (ref "R521") (pin "1") (pinfunction "1_1") (pintype "passive"))
    )
    (net (code "43") (name "Net-(DA503-D2)") (class "Default")
      (node (ref "C516") (pin "2") (pinfunction "2_2") (pintype "passive"))
      (node (ref "DA503") (pin "15") (pinfunction "D2_15") (pintype "passive"))
      (node (ref "R522") (pin "1") (pinfunction "1_1") (pintype "passive"))
    )
    (net (code "44") (name "Net-(DA503-S3)") (class "Default")
      (node (ref "C514") (pin "2") (pinfunction "2_2") (pintype "passive"))
      (node (ref "DA503") (pin "11") (pinfunction "S3_11") (pintype "passive"))
      (node (ref "R520") (pin "1") (pinfunction "1_1") (pintype "passive"))
      (node (ref "VD508") (pin "1") (pinfunction "C_1") (pintype "passive"))
      (node (ref "VD509") (pin "2") (pinfunction "A_2") (pintype "passive"))
    )
    (net (code "45") (name "Net-(DA504-+IN)") (class "Default")
      (node (ref "DA504") (pin "3") (pinfunction "+IN_3") (pintype "passive"))
      (node (ref "R529") (pin "2") (pinfunction "2_2") (pintype "passive"))
    )
    (net (code "46") (name "Net-(DA504--IN)") (class "Default")
      (node (ref "C518") (pin "1") (pinfunction "1_1") (pintype "passive"))
      (node (ref "DA504") (pin "2") (pinfunction "-IN_2") (pintype "passive"))
      (node (ref "R528") (pin "2") (pinfunction "2_2") (pintype "passive"))
    )
    (net (code "47") (name "Net-(DA505-E2)") (class "Default")
      (node (ref "DA505") (pin "16") (pinfunction "E2_16") (pintype "passive"))
      (node (ref "R531") (pin "2") (pinfunction "2_2") (pintype "passive"))
      (node (ref "VT509") (pin "3") (pinfunction "D_3") (pintype "passive"))
    )
    (net (code "48") (name "Net-(DA505-S1)") (class "Default")
      (node (ref "DA505") (pin "3") (pinfunction "S1_3") (pintype "passive"))
      (node (ref "R523") (pin "1") (pinfunction "1_1") (pintype "passive"))
      (node (ref "R524") (pin "2") (pinfunction "2_2") (pintype "passive"))
    )
    (net (code "49") (name "Net-(DA505-S2)") (class "Default")
      (node (ref "C519") (pin "1") (pinfunction "1_1") (pintype "passive"))
      (node (ref "DA505") (pin "14") (pinfunction "S2_14") (pintype "passive"))
    )
    (net (code "50") (name "Net-(DA505-S3)") (class "Default")
      (node (ref "DA505") (pin "11") (pinfunction "S3_11") (pintype "passive"))
      (node (ref "R526") (pin "1") (pinfunction "1_1") (pintype "passive"))
      (node (ref "R527") (pin "2") (pinfunction "2_2") (pintype "passive"))
    )
    (net (code "51") (name "Net-(DA505-S4)") (class "Default")
      (node (ref "DA505") (pin "6") (pinfunction "S4_6") (pintype "passive"))
      (node (ref "R525") (pin "1") (pinfunction "1_1") (pintype "passive"))
      (node (ref "R526") (pin "2") (pinfunction "2_2") (pintype "passive"))
    )
    (net (code "52") (name "Net-(DA506-+IN)") (class "Default")
      (node (ref "DA506") (pin "1") (pinfunction "+IN_1") (pintype "passive"))
      (node (ref "P506") (pin "1") (pinfunction "1_1") (pintype "passive"))
    )
    (net (code "53") (name "Net-(DA506--IN)") (class "Default")
      (node (ref "DA506") (pin "3") (pinfunction "-IN_3") (pintype "passive"))
      (node (ref "P505") (pin "1") (pinfunction "1_1") (pintype "passive"))
    )
    (net (code "54") (name "Net-(DA506-OUT)") (class "Default")
      (node (ref "DA506") (pin "4") (pinfunction "OUT_4") (pintype "passive"))
      (node (ref "P507") (pin "2") (pinfunction "2_2") (pintype "passive"))
    )
    (net (code "55") (name "Net-(K501-Pad14)") (class "Default")
      (node (ref "K501") (pin "14") (pinfunction "14_14") (pintype "passive"))
      (node (ref "R505") (pin "2") (pinfunction "2_2") (pintype "passive"))
    )
    (net (code "56") (name "Net-(R524-Pad1)") (class "Default")
      (node (ref "R524") (pin "1") (pinfunction "1_1") (pintype "passive"))
      (node (ref "R525") (pin "2") (pinfunction "2_2") (pintype "passive"))
    )
    (net (code "57") (name "Net-(VD504-A)") (class "Default")
      (node (ref "C511") (pin "2") (pinfunction "2_2") (pintype "passive"))
      (node (ref "R512") (pin "2") (pinfunction "2_2") (pintype "passive"))
      (node (ref "VD504") (pin "2") (pinfunction "A_2") (pintype "passive"))
      (node (ref "VD505") (pin "1") (pinfunction "K_1") (pintype "passive"))
    )
    (net (code "58") (name "Net-(VD504-K)") (class "Default")
      (node (ref "VD504") (pin "1") (pinfunction "K_1") (pintype "passive"))
      (node (ref "VT501") (pin "1") (pinfunction "B_1") (pintype "passive"))
      (node (ref "VT503") (pin "2") (pinfunction "C_2") (pintype "passive"))
      (node (ref "VT503") (pin "4") (pinfunction "C_4") (pintype "passive"))
      (node (ref "VT505") (pin "2") (pinfunction "C_2") (pintype "passive"))
      (node (ref "VT505") (pin "4") (pinfunction "C_4") (pintype "passive"))
    )
    (net (code "59") (name "Net-(VD505-A)") (class "Default")
      (node (ref "VD505") (pin "2") (pinfunction "A_2") (pintype "passive"))
      (node (ref "VT502") (pin "1") (pinfunction "B_1") (pintype "passive"))
      (node (ref "VT504") (pin "2") (pinfunction "C_2") (pintype "passive"))
      (node (ref "VT504") (pin "4") (pinfunction "C_4") (pintype "passive"))
      (node (ref "VT507") (pin "2") (pinfunction "C_2") (pintype "passive"))
      (node (ref "VT507") (pin "4") (pinfunction "C_4") (pintype "passive"))
    )
    (net (code "60") (name "Net-(VT501-E)") (class "Default")
      (node (ref "R509") (pin "2") (pinfunction "2_2") (pintype "passive"))
      (node (ref "R534") (pin "2") (pinfunction "2_2") (pintype "passive"))
      (node (ref "R535") (pin "2") (pinfunction "2_2") (pintype "passive"))
      (node (ref "VT501") (pin "3") (pinfunction "E_3") (pintype "passive"))
    )
    (net (code "61") (name "Net-(VT502-E)") (class "Default")
      (node (ref "R510") (pin "1") (pinfunction "1_1") (pintype "passive"))
      (node (ref "R536") (pin "2") (pinfunction "2_2") (pintype "passive"))
      (node (ref "R537") (pin "2") (pinfunction "2_2") (pintype "passive"))
      (node (ref "VT502") (pin "3") (pinfunction "E_3") (pintype "passive"))
    )
    (net (code "62") (name "Net-(VT503-B)") (class "Default")
      (node (ref "R534") (pin "1") (pinfunction "1_1") (pintype "passive"))
      (node (ref "VT503") (pin "1") (pinfunction "B_1") (pintype "passive"))
    )
    (net (code "63") (name "Net-(VT504-B)") (class "Default")
      (node (ref "R537") (pin "1") (pinfunction "1_1") (pintype "passive"))
      (node (ref "VT504") (pin "1") (pinfunction "B_1") (pintype "passive"))
    )
    (net (code "64") (name "Net-(VT505-B)") (class "Default")
      (node (ref "R515") (pin "2") (pinfunction "2_2") (pintype "passive"))
      (node (ref "VT505") (pin "1") (pinfunction "B_1") (pintype "passive"))
      (node (ref "VT506") (pin "1") (pinfunction "B_1") (pintype "passive"))
      (node (ref "VT506") (pin "2") (pinfunction "C_2") (pintype "passive"))
      (node (ref "VT506") (pin "4") (pinfunction "C_4") (pintype "passive"))
    )
    (net (code "65") (name "Net-(VT505-E)") (class "Default")
      (node (ref "R513") (pin "1") (pinfunction "1_1") (pintype "passive"))
      (node (ref "VT505") (pin "3") (pinfunction "E_3") (pintype "passive"))
    )
    (net (code "66") (name "Net-(VT506-E)") (class "Default")
      (node (ref "R514") (pin "1") (pinfunction "1_1") (pintype "passive"))
      (node (ref "VT506") (pin "3") (pinfunction "E_3") (pintype "passive"))
    )
    (net (code "67") (name "Net-(VT507-B)") (class "Default")
      (node (ref "R515") (pin "1") (pinfunction "1_1") (pintype "passive"))
      (node (ref "VT507") (pin "1") (pinfunction "B_1") (pintype "passive"))
      (node (ref "VT508") (pin "1") (pinfunction "B_1") (pintype "passive"))
      (node (ref "VT508") (pin "2") (pinfunction "C_2") (pintype "passive"))
      (node (ref "VT508") (pin "4") (pinfunction "C_4") (pintype "passive"))
    )
    (net (code "68") (name "Net-(VT507-E)") (class "Default")
      (node (ref "R516") (pin "2") (pinfunction "2_2") (pintype "passive"))
      (node (ref "VT507") (pin "3") (pinfunction "E_3") (pintype "passive"))
    )
    (net (code "69") (name "Net-(VT508-E)") (class "Default")
      (node (ref "R517") (pin "2") (pinfunction "2_2") (pintype "passive"))
      (node (ref "VT508") (pin "3") (pinfunction "E_3") (pintype "passive"))
    )
    (net (code "70") (name "Net-(VT509-G)") (class "Default")
      (node (ref "R532") (pin "2") (pinfunction "2_2") (pintype "passive"))
      (node (ref "R533") (pin "2") (pinfunction "2_2") (pintype "passive"))
      (node (ref "VT509") (pin "1") (pinfunction "G_1") (pintype "passive"))
    )
    (net (code "71") (name "U") (class "Default")
      (node (ref "C515") (pin "1") (pinfunction "1_1") (pintype "passive"))
      (node (ref "C516") (pin "1") (pinfunction "1_1") (pintype "passive"))
      (node (ref "DA502") (pin "6") (pinfunction "OUT_6") (pintype "passive"))
      (node (ref "KT502") (pin "1") (pinfunction "1_1") (pintype "passive"))
      (node (ref "R521") (pin "2") (pinfunction "2_2") (pintype "passive"))
      (node (ref "R522") (pin "2") (pinfunction "2_2") (pintype "passive"))
      (node (ref "R523") (pin "2") (pinfunction "2_2") (pintype "passive"))
    )
    (net (code "72") (name "UOC") (class "Default")
      (node (ref "C512") (pin "2") (pinfunction "2_2") (pintype "passive"))
      (node (ref "DA501") (pin "7") (pinfunction "OUT_7") (pintype "passive"))
      (node (ref "KT501") (pin "1") (pinfunction "1_1") (pintype "passive"))
      (node (ref "R504") (pin "2") (pinfunction "2_2") (pintype "passive"))
      (node (ref "R508") (pin "2") (pinfunction "2_2") (pintype "passive"))
      (node (ref "R511") (pin "1") (pinfunction "1_1") (pintype "passive"))
      (node (ref "R512") (pin "1") (pinfunction "1_1") (pintype "passive"))
      (node (ref "R518") (pin "1") (pinfunction "1_1") (pintype "passive"))
    )
    (net (code "73") (name "VS1+") (class "Default")
      (node (ref "DA506") (pin "5") (pinfunction "+U_5") (pintype "passive"))
      (node (ref "R535") (pin "1") (pinfunction "1_1") (pintype "passive"))
      (node (ref "VT503") (pin "3") (pinfunction "E_3") (pintype "passive"))
    )
    (net (code "74") (name "VS1-") (class "Default")
      (node (ref "DA506") (pin "2") (pinfunction "-U_2") (pintype "passive"))
      (node (ref "R536") (pin "1") (pinfunction "1_1") (pintype "passive"))
      (node (ref "VT504") (pin "3") (pinfunction "E_3") (pintype "passive"))
    )
    (net (code "75") (name "unconnected-(DA502-N-Pad1)") (class "Default")
      (node (ref "DA502") (pin "1") (pinfunction "N_1") (pintype "passive"))
    )
    (net (code "76") (name "unconnected-(DA502-N-Pad5)") (class "Default")
      (node (ref "DA502") (pin "5") (pinfunction "N_5") (pintype "passive"))
    )
    (net (code "77") (name "unconnected-(DA504-N-Pad1)") (class "Default")
      (node (ref "DA504") (pin "1") (pinfunction "N_1") (pintype "passive"))
    )
    (net (code "78") (name "unconnected-(DA504-N-Pad5)") (class "Default")
      (node (ref "DA504") (pin "5") (pinfunction "N_5") (pintype "passive"))
    )
  )
)
